# KAI_MEZON.net
KiCad netlist of a schematic drawn in Altium Designer
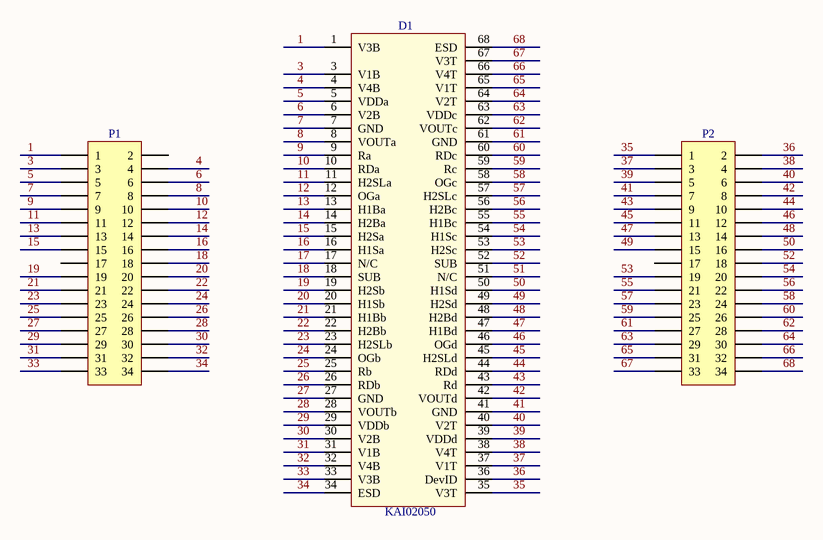
[diagram p0: KAI_MEZON.SchDoc]

(export (version "E")
  (design (tool "Eeschema 10.0.6"))
  (components
    (comp (ref "D1") (value "KAI02050") (footprint "KAI_02050") (libsource (lib "Schlib") (part "KAI-02050")))
    (comp (ref "P1")
      (value "Header 17X2")
      (footprint "HDR2X17")
      (description "Header, 17-Pin, Dual row")
      (fields (field (name "PUBLISHER") "Altium Limited"))
      (libsource (lib "Miscellaneous Connectors") (part "Header 17X2"))
    )
    (comp (ref "P2")
      (value "Header 17X2")
      (footprint "HDR2X17")
      (description "Header, 17-Pin, Dual row")
      (fields (field (name "PUBLISHER") "Altium Limited"))
      (libsource (lib "Miscellaneous Connectors") (part "Header 17X2"))
    )
  )
  (nets
    (net (code "1") (name "/1") (class "Default")
      (node (ref "D1") (pin "1") (pinfunction "V3B_1") (pintype "passive"))
      (node (ref "P1") (pin "1") (pinfunction "1_1") (pintype "passive"))
    )
    (net (code "2") (name "/3") (class "Default")
      (node (ref "D1") (pin "3") (pinfunction "V1B_3") (pintype "passive"))
      (node (ref "P1") (pin "3") (pinfunction "3_3") (pintype "passive"))
    )
    (net (code "3") (name "/4") (class "Default")
      (node (ref "D1") (pin "4") (pinfunction "V4B_4") (pintype "passive"))
      (node (ref "P1") (pin "4") (pinfunction "4_4") (pintype "passive"))
    )
    (net (code "4") (name "/5") (class "Default")
      (node (ref "D1") (pin "5") (pinfunction "VDDa_5") (pintype "passive"))
      (node (ref "P1") (pin "5") (pinfunction "5_5") (pintype "passive"))
    )
    (net (code "5") (name "/6") (class "Default")
      (node (ref "D1") (pin "6") (pinfunction "V2B_6") (pintype "passive"))
      (node (ref "P1") (pin "6") (pinfunction "6_6") (pintype "passive"))
    )
    (net (code "6") (name "/7") (class "Default")
      (node (ref "D1") (pin "7") (pinfunction "GND_7") (pintype "passive"))
      (node (ref "P1") (pin "7") (pinfunction "7_7") (pintype "passive"))
    )
    (net (code "7") (name "/8") (class "Default")
      (node (ref "D1") (pin "8") (pinfunction "VOUTa_8") (pintype "passive"))
      (node (ref "P1") (pin "8") (pinfunction "8_8") (pintype "passive"))
    )
    (net (code "8") (name "/9") (class "Default")
      (node (ref "D1") (pin "9") (pinfunction "Ra_9") (pintype "passive"))
      (node (ref "P1") (pin "9") (pinfunction "9_9") (pintype "passive"))
    )
    (net (code "9") (name "/10") (class "Default")
      (node (ref "D1") (pin "10") (pinfunction "RDa_10") (pintype "passive"))
      (node (ref "P1") (pin "10") (pinfunction "10_10") (pintype "passive"))
    )
    (net (code "10") (name "/11") (class "Default")
      (node (ref "D1") (pin "11") (pinfunction "H2SLa_11") (pintype "passive"))
      (node (ref "P1") (pin "11") (pinfunction "11_11") (pintype "passive"))
    )
    (net (code "11") (name "/12") (class "Default")
      (node (ref "D1") (pin "12") (pinfunction "OGa_12") (pintype "passive"))
      (node (ref "P1") (pin "12") (pinfunction "12_12") (pintype "passive"))
    )
    (net (code "12") (name "/13") (class "Default")
      (node (ref "D1") (pin "13") (pinfunction "H1Ba_13") (pintype "passive"))
      (node (ref "P1") (pin "13") (pinfunction "13_13") (pintype "passive"))
    )
    (net (code "13") (name "/14") (class "Default")
      (node (ref "D1") (pin "14") (pinfunction "H2Ba_14") (pintype "passive"))
      (node (ref "P1") (pin "14") (pinfunction "14_14") (pintype "passive"))
    )
    (net (code "14") (name "/15") (class "Default")
      (node (ref "D1") (pin "15") (pinfunction "H2Sa_15") (pintype "passive"))
      (node (ref "P1") (pin "15") (pinfunction "15_15") (pintype "passive"))
    )
    (net (code "15") (name "/16") (class "Default")
      (node (ref "D1") (pin "16") (pinfunction "H1Sa_16") (pintype "passive"))
      (node (ref "P1") (pin "16") (pinfunction "16_16") (pintype "passive"))
    )
    (net (code "16") (name "/17") (class "Default")
      (node (ref "D1") (pin "17") (pinfunction "N/C_17") (pintype "passive"))
    )
    (net (code "17") (name "/18") (class "Default")
      (node (ref "D1") (pin "18") (pinfunction "SUB_18") (pintype "passive"))
      (node (ref "P1") (pin "18") (pinfunction "18_18") (pintype "passive"))
    )
    (net (code "18") (name "/19") (class "Default")
      (node (ref "D1") (pin "19") (pinfunction "H2Sb_19") (pintype "passive"))
      (node (ref "P1") (pin "19") (pinfunction "19_19") (pintype "passive"))
    )
    (net (code "19") (name "/20") (class "Default")
      (node (ref "D1") (pin "20") (pinfunction "H1Sb_20") (pintype "passive"))
      (node (ref "P1") (pin "20") (pinfunction "20_20") (pintype "passive"))
    )
    (net (code "20") (name "/21") (class "Default")
      (node (ref "D1") (pin "21") (pinfunction "H1Bb_21") (pintype "passive"))
      (node (ref "P1") (pin "21") (pinfunction "21_21") (pintype "passive"))
    )
    (net (code "21") (name "/22") (class "Default")
      (node (ref "D1") (pin "22") (pinfunction "H2Bb_22") (pintype "passive"))
      (node (ref "P1") (pin "22") (pinfunction "22_22") (pintype "passive"))
    )
    (net (code "22") (name "/23") (class "Default")
      (node (ref "D1") (pin "23") (pinfunction "H2SLb_23") (pintype "passive"))
      (node (ref "P1") (pin "23") (pinfunction "23_23") (pintype "passive"))
    )
    (net (code "23") (name "/24") (class "Default")
      (node (ref "D1") (pin "24") (pinfunction "OGb_24") (pintype "passive"))
      (node (ref "P1") (pin "24") (pinfunction "24_24") (pintype "passive"))
    )
    (net (code "24") (name "/25") (class "Default")
      (node (ref "D1") (pin "25") (pinfunction "Rb_25") (pintype "passive"))
      (node (ref "P1") (pin "25") (pinfunction "25_25") (pintype "passive"))
    )
    (net (code "25") (name "/26") (class "Default")
      (node (ref "D1") (pin "26") (pinfunction "RDb_26") (pintype "passive"))
      (node (ref "P1") (pin "26") (pinfunction "26_26") (pintype "passive"))
    )
    (net (code "26") (name "/27") (class "Default")
      (node (ref "D1") (pin "27") (pinfunction "GND_27") (pintype "passive"))
      (node (ref "P1") (pin "27") (pinfunction "27_27") (pintype "passive"))
    )
    (net (code "27") (name "/28") (class "Default")
      (node (ref "D1") (pin "28") (pinfunction "VOUTb_28") (pintype "passive"))
      (node (ref "P1") (pin "28") (pinfunction "28_28") (pintype "passive"))
    )
    (net (code "28") (name "/29") (class "Default")
      (node (ref "D1") (pin "29") (pinfunction "VDDb_29") (pintype "passive"))
      (node (ref "P1") (pin "29") (pinfunction "29_29") (pintype "passive"))
    )
    (net (code "29") (name "/30") (class "Default")
      (node (ref "D1") (pin "30") (pinfunction "V2B_30") (pintype "passive"))
      (node (ref "P1") (pin "30") (pinfunction "30_30") (pintype "passive"))
    )
    (net (code "30") (name "/31") (class "Default")
      (node (ref "D1") (pin "31") (pinfunction "V1B_31") (pintype "passive"))
      (node (ref "P1") (pin "31") (pinfunction "31_31") (pintype "passive"))
    )
    (net (code "31") (name "/32") (class "Default")
      (node (ref "D1") (pin "32") (pinfunction "V4B_32") (pintype "passive"))
      (node (ref "P1") (pin "32") (pinfunction "32_32") (pintype "passive"))
    )
    (net (code "32") (name "/33") (class "Default")
      (node (ref "D1") (pin "33") (pinfunction "V3B_33") (pintype "passive"))
      (node (ref "P1") (pin "33") (pinfunction "33_33") (pintype "passive"))
    )
    (net (code "33") (name "/34") (class "Default")
      (node (ref "D1") (pin "34") (pinfunction "ESD_34") (pintype "passive"))
      (node (ref "P1") (pin "34") (pinfunction "34_34") (pintype "passive"))
    )
    (net (code "34") (name "/35") (class "Default")
      (node (ref "D1") (pin "35") (pinfunction "V3T_35") (pintype "passive"))
      (node (ref "P2") (pin "1") (pinfunction "1_1") (pintype "passive"))
    )
    (net (code "35") (name "/36") (class "Default")
      (node (ref "D1") (pin "36") (pinfunction "DevID_36") (pintype "passive"))
      (node (ref "P2") (pin "2") (pinfunction "2_2") (pintype "passive"))
    )
    (net (code "36") (name "/37") (class "Default")
      (node (ref "D1") (pin "37") (pinfunction "V1T_37") (pintype "passive"))
      (node (ref "P2") (pin "3") (pinfunction "3_3") (pintype "passive"))
    )
    (net (code "37") (name "/38") (class "Default")
      (node (ref "D1") (pin "38") (pinfunction "V4T_38") (pintype "passive"))
      (node (ref "P2") (pin "4") (pinfunction "4_4") (pintype "passive"))
    )
    (net (code "38") (name "/39") (class "Default")
      (node (ref "D1") (pin "39") (pinfunction "VDDd_39") (pintype "passive"))
      (node (ref "P2") (pin "5") (pinfunction "5_5") (pintype "passive"))
    )
    (net (code "39") (name "/40") (class "Default")
      (node (ref "D1") (pin "40") (pinfunction "V2T_40") (pintype "passive"))
      (node (ref "P2") (pin "6") (pinfunction "6_6") (pintype "passive"))
    )
    (net (code "40") (name "/41") (class "Default")
      (node (ref "D1") (pin "41") (pinfunction "GND_41") (pintype "passive"))
      (node (ref "P2") (pin "7") (pinfunction "7_7") (pintype "passive"))
    )
    (net (code "41") (name "/42") (class "Default")
      (node (ref "D1") (pin "42") (pinfunction "VOUTd_42") (pintype "passive"))
      (node (ref "P2") (pin "8") (pinfunction "8_8") (pintype "passive"))
    )
    (net (code "42") (name "/43") (class "Default")
      (node (ref "D1") (pin "43") (pinfunction "Rd_43") (pintype "passive"))
      (node (ref "P2") (pin "9") (pinfunction "9_9") (pintype "passive"))
    )
    (net (code "43") (name "/44") (class "Default")
      (node (ref "D1") (pin "44") (pinfunction "RDd_44") (pintype "passive"))
      (node (ref "P2") (pin "10") (pinfunction "10_10") (pintype "passive"))
    )
    (net (code "44") (name "/45") (class "Default")
      (node (ref "D1") (pin "45") (pinfunction "H2SLd_45") (pintype "passive"))
      (node (ref "P2") (pin "11") (pinfunction "11_11") (pintype "passive"))
    )
    (net (code "45") (name "/46") (class "Default")
      (node (ref "D1") (pin "46") (pinfunction "OGd_46") (pintype "passive"))
      (node (ref "P2") (pin "12") (pinfunction "12_12") (pintype "passive"))
    )
    (net (code "46") (name "/47") (class "Default")
      (node (ref "D1") (pin "47") (pinfunction "H1Bd_47") (pintype "passive"))
      (node (ref "P2") (pin "13") (pinfunction "13_13") (pintype "passive"))
    )
    (net (code "47") (name "/48") (class "Default")
      (node (ref "D1") (pin "48") (pinfunction "H2Bd_48") (pintype "passive"))
      (node (ref "P2") (pin "14") (pinfunction "14_14") (pintype "passive"))
    )
    (net (code "48") (name "/49") (class "Default")
      (node (ref "D1") (pin "49") (pinfunction "H2Sd_49") (pintype "passive"))
      (node (ref "P2") (pin "15") (pinfunction "15_15") (pintype "passive"))
    )
    (net (code "49") (name "/50") (class "Default")
      (node (ref "D1") (pin "50") (pinfunction "H1Sd_50") (pintype "passive"))
      (node (ref "P2") (pin "16") (pinfunction "16_16") (pintype "passive"))
    )
    (net (code "50") (name "/51") (class "Default")
      (node (ref "D1") (pin "51") (pinfunction "N/C_51") (pintype "passive"))
    )
    (net (code "51") (name "/52") (class "Default")
      (node (ref "D1") (pin "52") (pinfunction "SUB_52") (pintype "passive"))
      (node (ref "P2") (pin "18") (pinfunction "18_18") (pintype "passive"))
    )
    (net (code "52") (name "/53") (class "Default")
      (node (ref "D1") (pin "53") (pinfunction "H2Sc_53") (pintype "passive"))
      (node (ref "P2") (pin "19") (pinfunction "19_19") (pintype "passive"))
    )
    (net (code "53") (name "/54") (class "Default")
      (node (ref "D1") (pin "54") (pinfunction "H1Sc_54") (pintype "passive"))
      (node (ref "P2") (pin "20") (pinfunction "20_20") (pintype "passive"))
    )
    (net (code "54") (name "/55") (class "Default")
      (node (ref "D1") (pin "55") (pinfunction "H1Bc_55") (pintype "passive"))
      (node (ref "P2") (pin "21") (pinfunction "21_21") (pintype "passive"))
    )
    (net (code "55") (name "/56") (class "Default")
      (node (ref "D1") (pin "56") (pinfunction "H2Bc_56") (pintype "passive"))
      (node (ref "P2") (pin "22") (pinfunction "22_22") (pintype "passive"))
    )
    (net (code "56") (name "/57") (class "Default")
      (node (ref "D1") (pin "57") (pinfunction "H2SLc_57") (pintype "passive"))
      (node (ref "P2") (pin "23") (pinfunction "23_23") (pintype "passive"))
    )
    (net (code "57") (name "/58") (class "Default")
      (node (ref "D1") (pin "58") (pinfunction "OGc_58") (pintype "passive"))
      (node (ref "P2") (pin "24") (pinfunction "24_24") (pintype "passive"))
    )
    (net (code "58") (name "/59") (class "Default")
      (node (ref "D1") (pin "59") (pinfunction "Rc_59") (pintype "passive"))
      (node (ref "P2") (pin "25") (pinfunction "25_25") (pintype "passive"))
    )
    (net (code "59") (name "/60") (class "Default")
      (node (ref "D1") (pin "60") (pinfunction "RDc_60") (pintype "passive"))
      (node (ref "P2") (pin "26") (pinfunction "26_26") (pintype "passive"))
    )
    (net (code "60") (name "/61") (class "Default")
      (node (ref "D1") (pin "61") (pinfunction "GND_61") (pintype "passive"))
      (node (ref "P2") (pin "27") (pinfunction "27_27") (pintype "passive"))
    )
    (net (code "61") (name "/62") (class "Default")
      (node (ref "D1") (pin "62") (pinfunction "VOUTc_62") (pintype "passive"))
      (node (ref "P2") (pin "28") (pinfunction "28_28") (pintype "passive"))
    )
    (net (code "62") (name "/63") (class "Default")
      (node (ref "D1") (pin "63") (pinfunction "VDDc_63") (pintype "passive"))
      (node (ref "P2") (pin "29") (pinfunction "29_29") (pintype "passive"))
    )
    (net (code "63") (name "/64") (class "Default")
      (node (ref "D1") (pin "64") (pinfunction "V2T_64") (pintype "passive"))
      (node (ref "P2") (pin "30") (pinfunction "30_30") (pintype "passive"))
    )
    (net (code "64") (name "/65") (class "Default")
      (node (ref "D1") (pin "65") (pinfunction "V1T_65") (pintype "passive"))
      (node (ref "P2") (pin "31") (pinfunction "31_31") (pintype "passive"))
    )
    (net (code "65") (name "/66") (class "Default")
      (node (ref "D1") (pin "66") (pinfunction "V4T_66") (pintype "passive"))
      (node (ref "P2") (pin "32") (pinfunction "32_32") (pintype "passive"))
    )
    (net (code "66") (name "/67") (class "Default")
      (node (ref "D1") (pin "67") (pinfunction "V3T_67") (pintype "passive"))
      (node (ref "P2") (pin "33") (pinfunction "33_33") (pintype "passive"))
    )
    (net (code "67") (name "/68") (class "Default")
      (node (ref "D1") (pin "68") (pinfunction "ESD_68") (pintype "passive"))
      (node (ref "P2") (pin "34") (pinfunction "34_34") (pintype "passive"))
    )
    (net (code "68") (name "unconnected-(P1-Pad2)") (class "Default")
      (node (ref "P1") (pin "2") (pinfunction "2_2") (pintype "passive"))
    )
    (net (code "69") (name "unconnected-(P1-Pad17)") (class "Default")
      (node (ref "P1") (pin "17") (pinfunction "17_17") (pintype "passive"))
    )
    (net (code "70") (name "unconnected-(P2-Pad17)") (class "Default")
      (node (ref "P2") (pin "17") (pinfunction "17_17") (pintype "passive"))
    )
  )
)
